# 44con2014.net
KiCad netlist of a schematic drawn in EAGLE
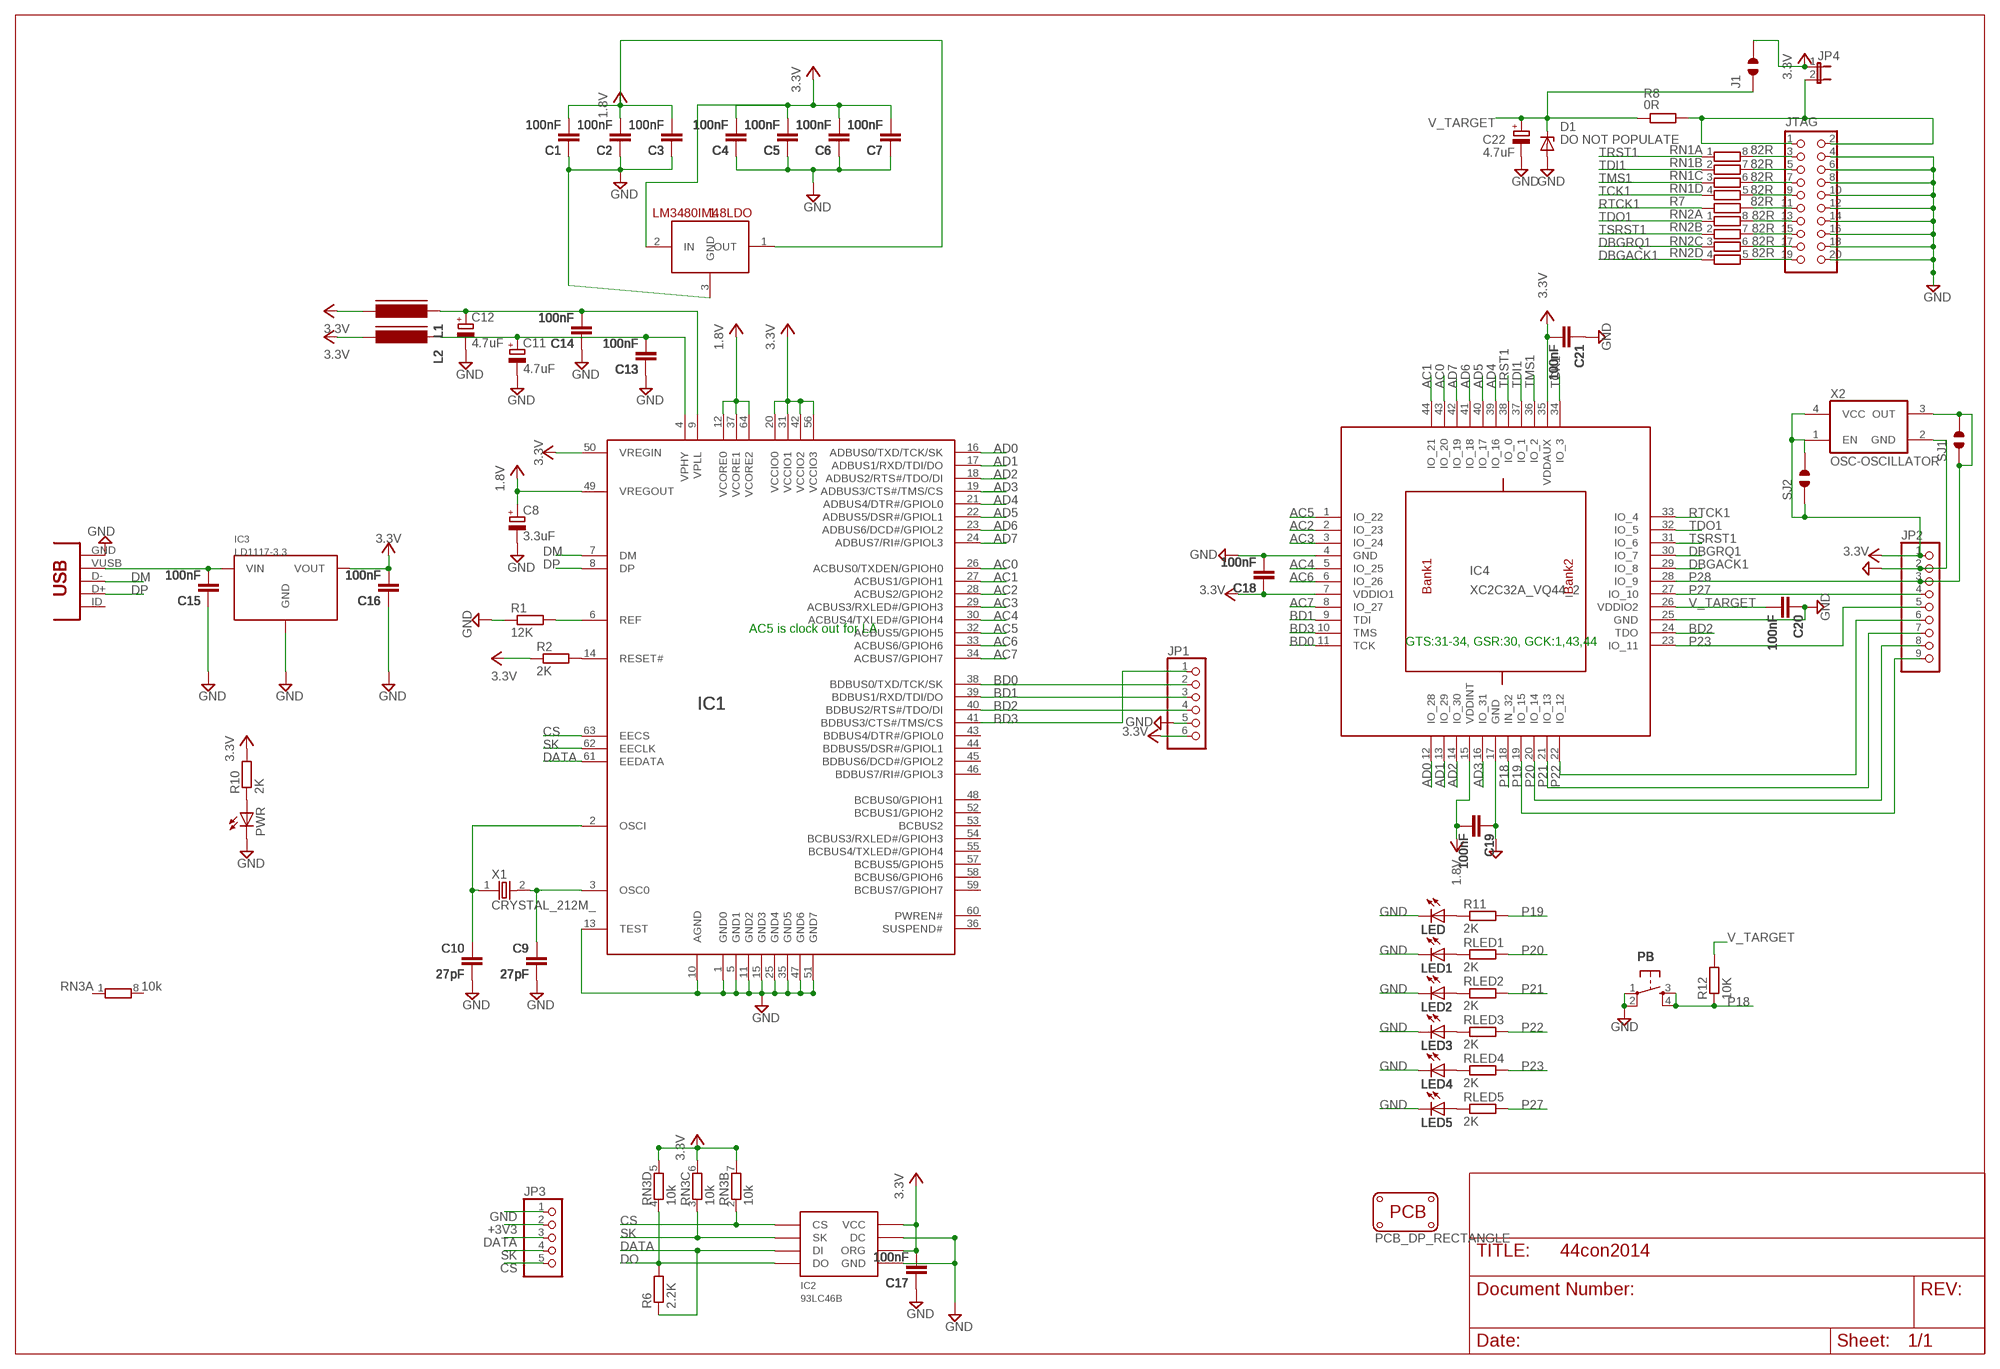
[diagram p0: schematic, sheet 1]

(export (version "E")
  (design (tool "Eeschema 10.0.6"))
  (components
    (comp (ref "1.8LDO")
      (value "LM3480IM4")
      (footprint "eagle-import:SOT23-3")
      (libsource (lib "eagle-import") (part "LM3480IM4"))
    )
    (comp (ref "C1")
      (value "100nF")
      (footprint "eagle-import:C603")
      (libsource (lib "eagle-import") (part "CAPC603"))
    )
    (comp (ref "C2")
      (value "100nF")
      (footprint "eagle-import:C603")
      (libsource (lib "eagle-import") (part "CAPC603"))
    )
    (comp (ref "C3")
      (value "100nF")
      (footprint "eagle-import:C603")
      (libsource (lib "eagle-import") (part "CAPC603"))
    )
    (comp (ref "C4")
      (value "100nF")
      (footprint "eagle-import:C603")
      (libsource (lib "eagle-import") (part "CAPC603"))
    )
    (comp (ref "C5")
      (value "100nF")
      (footprint "eagle-import:C603")
      (libsource (lib "eagle-import") (part "CAPC603"))
    )
    (comp (ref "C6")
      (value "100nF")
      (footprint "eagle-import:C603")
      (libsource (lib "eagle-import") (part "CAPC603"))
    )
    (comp (ref "C7")
      (value "100nF")
      (footprint "eagle-import:C603")
      (libsource (lib "eagle-import") (part "CAPC603"))
    )
    (comp (ref "C8")
      (value "3.3uF")
      (footprint "eagle-import:SMC_A")
      (libsource (lib "eagle-import") (part "CAP_POLSMC_A"))
    )
    (comp (ref "C9")
      (value "27pF")
      (footprint "eagle-import:C603")
      (libsource (lib "eagle-import") (part "CAPC603"))
    )
    (comp (ref "C10")
      (value "27pF")
      (footprint "eagle-import:C603")
      (libsource (lib "eagle-import") (part "CAPC603"))
    )
    (comp (ref "C11")
      (value "4.7uF")
      (footprint "eagle-import:SMC_A")
      (libsource (lib "eagle-import") (part "CAP_POLSMC_A"))
    )
    (comp (ref "C12")
      (value "4.7uF")
      (footprint "eagle-import:SMC_A")
      (libsource (lib "eagle-import") (part "CAP_POLSMC_A"))
    )
    (comp (ref "C13")
      (value "100nF")
      (footprint "eagle-import:C603")
      (libsource (lib "eagle-import") (part "CAPC603"))
    )
    (comp (ref "C14")
      (value "100nF")
      (footprint "eagle-import:C603")
      (libsource (lib "eagle-import") (part "CAPC603"))
    )
    (comp (ref "C15")
      (value "100nF")
      (footprint "eagle-import:C603")
      (libsource (lib "eagle-import") (part "CAPC603"))
    )
    (comp (ref "C16")
      (value "100nF")
      (footprint "eagle-import:C603")
      (libsource (lib "eagle-import") (part "CAPC603"))
    )
    (comp (ref "C17")
      (value "100nF")
      (footprint "eagle-import:C603")
      (libsource (lib "eagle-import") (part "CAPC603"))
    )
    (comp (ref "C18")
      (value "100nF")
      (footprint "eagle-import:C603")
      (libsource (lib "eagle-import") (part "CAPC603"))
    )
    (comp (ref "C19")
      (value "100nF")
      (footprint "eagle-import:C603")
      (libsource (lib "eagle-import") (part "CAPC603"))
    )
    (comp (ref "C20")
      (value "100nF")
      (footprint "eagle-import:C603")
      (libsource (lib "eagle-import") (part "CAPC603"))
    )
    (comp (ref "C21")
      (value "100nF")
      (footprint "eagle-import:C603")
      (libsource (lib "eagle-import") (part "CAPC603"))
    )
    (comp (ref "C22")
      (value "4.7uF")
      (footprint "eagle-import:SMC_A")
      (libsource (lib "eagle-import") (part "CAP_POLSMC_A"))
    )
    (comp (ref "D1")
      (value "DO NOT POPULATE")
      (footprint "eagle-import:SOD-123")
      (libsource (lib "eagle-import") (part "ZENERSOD-123"))
    )
    (comp (ref "IC1")
      (value "FT2232H")
      (footprint "eagle-import:LQFP64")
      (libsource (lib "eagle-import") (part "FT2232H"))
    )
    (comp (ref "IC2")
      (value "93LC46B")
      (footprint "eagle-import:SOIC8")
      (libsource (lib "eagle-import") (part "93C46"))
    )
    (comp (ref "IC3")
      (value "LD1117-3.3")
      (footprint "eagle-import:SOT223")
      (libsource (lib "eagle-import") (part "LD1117-3.3"))
    )
    (comp (ref "IC4")
      (value "XC2C32A_VQ44_2")
      (footprint "eagle-import:VQ44")
      (libsource (lib "eagle-import") (part "XC2C32A_VQ44_2"))
    )
    (comp (ref "J1")
      (value "JUMPER_SOLDER_1X2")
      (footprint "eagle-import:JUMPER_SOLDER_1X2")
      (libsource (lib "eagle-import") (part "JUMPER_SOLDER_1X2"))
    )
    (comp (ref "JP1")
      (value "PINHD-1X6")
      (footprint "eagle-import:1X06")
      (libsource (lib "eagle-import") (part "PINHD-1X6"))
    )
    (comp (ref "JP2")
      (value "PINHD-1X9")
      (footprint "eagle-import:1X09")
      (libsource (lib "eagle-import") (part "PINHD-1X9"))
    )
    (comp (ref "JP3")
      (value "PINHD-1X5")
      (footprint "eagle-import:1X05")
      (libsource (lib "eagle-import") (part "PINHD-1X5"))
    )
    (comp (ref "JP4")
      (value "JP1EJP")
      (footprint "eagle-import:1X02")
      (libsource (lib "eagle-import") (part "JP1EJP"))
    )
    (comp (ref "JTAG")
      (value "CON_HEADER_2X10-SHROUDED")
      (footprint "eagle-import:PINSHRD_PTH_2X10")
      (libsource (lib "eagle-import") (part "CON_HEADER_2X10-SHROUDED"))
    )
    (comp (ref "L1")
      (value "FERRITE_BEAD603")
      (footprint "eagle-import:FB603")
      (libsource (lib "eagle-import") (part "FERRITE_BEAD603"))
    )
    (comp (ref "L2")
      (value "FERRITE_BEAD603")
      (footprint "eagle-import:FB603")
      (libsource (lib "eagle-import") (part "FERRITE_BEAD603"))
    )
    (comp (ref "LED")
      (value "LED805")
      (footprint "eagle-import:LED-805")
      (libsource (lib "eagle-import") (part "LED805"))
    )
    (comp (ref "LED1")
      (value "LED805")
      (footprint "eagle-import:LED-805")
      (libsource (lib "eagle-import") (part "LED805"))
    )
    (comp (ref "LED2")
      (value "LED805")
      (footprint "eagle-import:LED-805")
      (libsource (lib "eagle-import") (part "LED805"))
    )
    (comp (ref "LED3")
      (value "LED805")
      (footprint "eagle-import:LED-805")
      (libsource (lib "eagle-import") (part "LED805"))
    )
    (comp (ref "LED4")
      (value "LED805")
      (footprint "eagle-import:LED-805")
      (libsource (lib "eagle-import") (part "LED805"))
    )
    (comp (ref "LED5")
      (value "LED805")
      (footprint "eagle-import:LED-805")
      (libsource (lib "eagle-import") (part "LED805"))
    )
    (comp (ref "PB")
      (value "SW-SMD-SMALL")
      (footprint "eagle-import:TACT_SWITCH_SMALL")
      (libsource (lib "eagle-import") (part "SW-SMD-SMALL"))
    )
    (comp (ref "PCB3")
      (value "PCB_DP_RECTANGLE")
      (footprint "eagle-import:44CON2014")
      (libsource (lib "eagle-import") (part "PCB_DP_RECTANGLE"))
    )
    (comp (ref "PWR")
      (value "LEDCHIPLED_0805")
      (footprint "eagle-import:CHIPLED_0805")
      (libsource (lib "eagle-import") (part "LEDCHIPLED_0805"))
    )
    (comp (ref "R1")
      (value "12K")
      (footprint "eagle-import:R603")
      (libsource (lib "eagle-import") (part "RESISTORR603"))
    )
    (comp (ref "R2")
      (value "2K")
      (footprint "eagle-import:R603")
      (libsource (lib "eagle-import") (part "RESISTORR603"))
    )
    (comp (ref "R6")
      (value "2.2K")
      (footprint "eagle-import:R603")
      (libsource (lib "eagle-import") (part "RESISTORR603"))
    )
    (comp (ref "R7")
      (value "82R")
      (footprint "eagle-import:R603")
      (libsource (lib "eagle-import") (part "RESISTORR603"))
    )
    (comp (ref "R8")
      (value "0R")
      (footprint "eagle-import:R1206")
      (libsource (lib "eagle-import") (part "RESISTORR1206"))
    )
    (comp (ref "R10")
      (value "2K")
      (footprint "eagle-import:R603")
      (libsource (lib "eagle-import") (part "RESISTORR603"))
    )
    (comp (ref "R11")
      (value "2K")
      (footprint "eagle-import:R603")
      (libsource (lib "eagle-import") (part "RESISTORR603"))
    )
    (comp (ref "R12")
      (value "10K")
      (footprint "eagle-import:R603")
      (libsource (lib "eagle-import") (part "RESISTORR603"))
    )
    (comp (ref "RLED1")
      (value "2K")
      (footprint "eagle-import:R603")
      (libsource (lib "eagle-import") (part "RESISTORR603"))
    )
    (comp (ref "RLED2")
      (value "2K")
      (footprint "eagle-import:R603")
      (libsource (lib "eagle-import") (part "RESISTORR603"))
    )
    (comp (ref "RLED3")
      (value "2K")
      (footprint "eagle-import:R603")
      (libsource (lib "eagle-import") (part "RESISTORR603"))
    )
    (comp (ref "RLED4")
      (value "2K")
      (footprint "eagle-import:R603")
      (libsource (lib "eagle-import") (part "RESISTORR603"))
    )
    (comp (ref "RLED5")
      (value "2K")
      (footprint "eagle-import:R603")
      (libsource (lib "eagle-import") (part "RESISTORR603"))
    )
    (comp (ref "RN1")
      (value "82R")
      (footprint "eagle-import:RN8P-4R-CRA06S")
      (libsource (lib "eagle-import") (part "RNETWORK"))
    )
    (comp (ref "RN2")
      (value "82R")
      (footprint "eagle-import:RN8P-4R-CRA06S")
      (libsource (lib "eagle-import") (part "RNETWORK"))
    )
    (comp (ref "RN3")
      (value "10k")
      (footprint "eagle-import:RN8P-4R-CRA06S")
      (libsource (lib "eagle-import") (part "RNETWORK"))
    )
    (comp (ref "SJ1")
      (value "JUMPER_SOLDER_1X2")
      (footprint "eagle-import:JUMPER_SOLDER_1X2")
      (libsource (lib "eagle-import") (part "JUMPER_SOLDER_1X2"))
    )
    (comp (ref "SJ2")
      (value "JUMPER_SOLDER_1X2")
      (footprint "eagle-import:JUMPER_SOLDER_1X2")
      (libsource (lib "eagle-import") (part "JUMPER_SOLDER_1X2"))
    )
    (comp (ref "USB")
      (value "CON-USB-MINI-BUSB1")
      (footprint "eagle-import:CONN_USB_MINI-B")
      (libsource (lib "eagle-import") (part "CON-USB-MINI-BUSB1"))
    )
    (comp (ref "X1")
      (value "CRYSTAL_212M_")
      (footprint "eagle-import:XTAL_4X6")
      (libsource (lib "eagle-import") (part "OSC-XTAL-12M"))
    )
    (comp (ref "X2")
      (value "OSC-OSCILLATOR")
      (footprint "eagle-import:OSCILLATOR_7X5_SMD")
      (libsource (lib "eagle-import") (part "OSC-OSCILLATOR"))
    )
  )
  (nets
    (net (code "1") (name "/AC0") (class "Default")
      (node (ref "IC1") (pin "26") (pinfunction "ACBUS0/TXDEN/GPIOH0_26") (pintype "bidirectional"))
      (node (ref "IC4") (pin "43") (pinfunction "IO_20_43") (pintype "bidirectional"))
    )
    (net (code "2") (name "/AC1") (class "Default")
      (node (ref "IC1") (pin "27") (pinfunction "ACBUS1/GPIOH1_27") (pintype "bidirectional"))
      (node (ref "IC4") (pin "44") (pinfunction "IO_21_44") (pintype "bidirectional"))
    )
    (net (code "3") (name "/AC2") (class "Default")
      (node (ref "IC1") (pin "28") (pinfunction "ACBUS2/GPIOH2_28") (pintype "bidirectional"))
      (node (ref "IC4") (pin "2") (pinfunction "IO_23_2") (pintype "bidirectional"))
    )
    (net (code "4") (name "/AC3") (class "Default")
      (node (ref "IC1") (pin "29") (pinfunction "ACBUS3/RXLED#/GPIOH3_29") (pintype "bidirectional"))
      (node (ref "IC4") (pin "3") (pinfunction "IO_24_3") (pintype "bidirectional"))
    )
    (net (code "5") (name "/AC4") (class "Default")
      (node (ref "IC1") (pin "30") (pinfunction "ACBUS4/TXLED#/GPIOH4_30") (pintype "bidirectional"))
      (node (ref "IC4") (pin "5") (pinfunction "IO_25_5") (pintype "bidirectional"))
    )
    (net (code "6") (name "/AC5") (class "Default")
      (node (ref "IC1") (pin "32") (pinfunction "ACBUS5/GPIOH5_32") (pintype "bidirectional"))
      (node (ref "IC4") (pin "1") (pinfunction "IO_22_1") (pintype "bidirectional"))
    )
    (net (code "7") (name "/AC6") (class "Default")
      (node (ref "IC1") (pin "33") (pinfunction "ACBUS6/GPIOH6_33") (pintype "bidirectional"))
      (node (ref "IC4") (pin "6") (pinfunction "IO_26_6") (pintype "bidirectional"))
    )
    (net (code "8") (name "/AC7") (class "Default")
      (node (ref "IC1") (pin "34") (pinfunction "ACBUS7/GPIOH7_34") (pintype "bidirectional"))
      (node (ref "IC4") (pin "8") (pinfunction "IO_27_8") (pintype "bidirectional"))
    )
    (net (code "9") (name "/AD0") (class "Default")
      (node (ref "IC1") (pin "16") (pinfunction "ADBUS0/TXD/TCK/SK_16") (pintype "bidirectional"))
      (node (ref "IC4") (pin "12") (pinfunction "IO_28_12") (pintype "bidirectional"))
    )
    (net (code "10") (name "/AD1") (class "Default")
      (node (ref "IC1") (pin "17") (pinfunction "ADBUS1/RXD/TDI/DO_17") (pintype "bidirectional"))
      (node (ref "IC4") (pin "13") (pinfunction "IO_29_13") (pintype "bidirectional"))
    )
    (net (code "11") (name "/AD2") (class "Default")
      (node (ref "IC1") (pin "18") (pinfunction "ADBUS2/RTS#/TDO/DI_18") (pintype "bidirectional"))
      (node (ref "IC4") (pin "14") (pinfunction "IO_30_14") (pintype "bidirectional"))
    )
    (net (code "12") (name "/AD3") (class "Default")
      (node (ref "IC1") (pin "19") (pinfunction "ADBUS3/CTS#/TMS/CS_19") (pintype "bidirectional"))
      (node (ref "IC4") (pin "16") (pinfunction "IO_31_16") (pintype "bidirectional"))
    )
    (net (code "13") (name "/AD4") (class "Default")
      (node (ref "IC1") (pin "21") (pinfunction "ADBUS4/DTR#/GPIOL0_21") (pintype "bidirectional"))
      (node (ref "IC4") (pin "39") (pinfunction "IO_16_39") (pintype "bidirectional"))
    )
    (net (code "14") (name "/AD5") (class "Default")
      (node (ref "IC1") (pin "22") (pinfunction "ADBUS5/DSR#/GPIOL1_22") (pintype "bidirectional"))
      (node (ref "IC4") (pin "40") (pinfunction "IO_17_40") (pintype "bidirectional"))
    )
    (net (code "15") (name "/AD6") (class "Default")
      (node (ref "IC1") (pin "23") (pinfunction "ADBUS6/DCD#/GPIOL2_23") (pintype "bidirectional"))
      (node (ref "IC4") (pin "41") (pinfunction "IO_18_41") (pintype "bidirectional"))
    )
    (net (code "16") (name "/AD7") (class "Default")
      (node (ref "IC1") (pin "24") (pinfunction "ADBUS7/RI#/GPIOL3_24") (pintype "bidirectional"))
      (node (ref "IC4") (pin "42") (pinfunction "IO_19_42") (pintype "bidirectional"))
    )
    (net (code "17") (name "/BD0") (class "Default")
      (node (ref "IC1") (pin "38") (pinfunction "BDBUS0/TXD/TCK/SK_38") (pintype "bidirectional"))
      (node (ref "IC4") (pin "11") (pinfunction "TCK_11") (pintype "input"))
      (node (ref "JP1") (pin "2") (pinfunction "2_2") (pintype "passive"))
    )
    (net (code "18") (name "/BD1") (class "Default")
      (node (ref "IC1") (pin "39") (pinfunction "BDBUS1/RXD/TDI/DO_39") (pintype "bidirectional"))
      (node (ref "IC4") (pin "9") (pinfunction "TDI_9") (pintype "input"))
      (node (ref "JP1") (pin "3") (pinfunction "3_3") (pintype "passive"))
    )
    (net (code "19") (name "/BD2") (class "Default")
      (node (ref "IC1") (pin "40") (pinfunction "BDBUS2/RTS#/TDO/DI_40") (pintype "bidirectional"))
      (node (ref "IC4") (pin "24") (pinfunction "TDO_24") (pintype "output"))
      (node (ref "JP1") (pin "4") (pinfunction "4_4") (pintype "passive"))
    )
    (net (code "20") (name "/BD3") (class "Default")
      (node (ref "IC1") (pin "41") (pinfunction "BDBUS3/CTS#/TMS/CS_41") (pintype "bidirectional"))
      (node (ref "IC4") (pin "10") (pinfunction "TMS_10") (pintype "input"))
      (node (ref "JP1") (pin "1") (pinfunction "1_1") (pintype "passive"))
    )
    (net (code "21") (name "/CS") (class "Default")
      (node (ref "IC1") (pin "63") (pinfunction "EECS_63") (pintype "bidirectional"))
      (node (ref "IC2") (pin "1") (pinfunction "CS_1") (pintype "bidirectional"))
      (node (ref "JP3") (pin "5") (pinfunction "5_5") (pintype "passive"))
      (node (ref "RN3") (pin "2") (pinfunction "1_2") (pintype "passive"))
    )
    (net (code "22") (name "/DATA") (class "Default")
      (node (ref "IC1") (pin "61") (pinfunction "EEDATA_61") (pintype "bidirectional"))
      (node (ref "IC2") (pin "3") (pinfunction "DI_3") (pintype "bidirectional"))
      (node (ref "JP3") (pin "3") (pinfunction "3_3") (pintype "passive"))
      (node (ref "R6") (pin "1") (pinfunction "1_1") (pintype "passive"))
    )
    (net (code "23") (name "/DBGACK1") (class "Default")
      (node (ref "IC4") (pin "29") (pinfunction "IO_8_29") (pintype "bidirectional"))
      (node (ref "RN2") (pin "4") (pinfunction "1_4") (pintype "passive"))
    )
    (net (code "24") (name "/DBGRQ1") (class "Default")
      (node (ref "IC4") (pin "30") (pinfunction "IO_7_30") (pintype "bidirectional"))
      (node (ref "RN2") (pin "3") (pinfunction "1_3") (pintype "passive"))
    )
    (net (code "25") (name "/DM") (class "Default")
      (node (ref "IC1") (pin "7") (pinfunction "DM_7") (pintype "bidirectional"))
      (node (ref "USB") (pin "D-") (pinfunction "D-_D-") (pintype "bidirectional"))
    )
    (net (code "26") (name "/DO") (class "Default")
      (node (ref "IC2") (pin "4") (pinfunction "DO_4") (pintype "bidirectional"))
      (node (ref "R6") (pin "2") (pinfunction "2_2") (pintype "passive"))
      (node (ref "RN3") (pin "4") (pinfunction "1_4") (pintype "passive"))
    )
    (net (code "27") (name "/DP") (class "Default")
      (node (ref "IC1") (pin "8") (pinfunction "DP_8") (pintype "bidirectional"))
      (node (ref "USB") (pin "D+") (pinfunction "D+_D+") (pintype "bidirectional"))
    )
    (net (code "28") (name "/P18") (class "Default")
      (node (ref "IC4") (pin "18") (pinfunction "IN_32_18") (pintype "input"))
      (node (ref "PB") (pin "3") (pinfunction "3_3") (pintype "passive"))
      (node (ref "PB") (pin "4") (pinfunction "4_4") (pintype "passive"))
      (node (ref "R12") (pin "1") (pinfunction "1_1") (pintype "passive"))
    )
    (net (code "29") (name "/P19") (class "Default")
      (node (ref "IC4") (pin "19") (pinfunction "IO_15_19") (pintype "bidirectional"))
      (node (ref "JP2") (pin "9") (pinfunction "9_9") (pintype "passive"))
      (node (ref "R11") (pin "2") (pinfunction "2_2") (pintype "passive"))
    )
    (net (code "30") (name "/P20") (class "Default")
      (node (ref "IC4") (pin "20") (pinfunction "IO_14_20") (pintype "bidirectional"))
      (node (ref "JP2") (pin "8") (pinfunction "8_8") (pintype "passive"))
      (node (ref "RLED1") (pin "2") (pinfunction "2_2") (pintype "passive"))
    )
    (net (code "31") (name "/P21") (class "Default")
      (node (ref "IC4") (pin "21") (pinfunction "IO_13_21") (pintype "bidirectional"))
      (node (ref "JP2") (pin "7") (pinfunction "7_7") (pintype "passive"))
      (node (ref "RLED2") (pin "2") (pinfunction "2_2") (pintype "passive"))
    )
    (net (code "32") (name "/P22") (class "Default")
      (node (ref "IC4") (pin "22") (pinfunction "IO_12_22") (pintype "bidirectional"))
      (node (ref "JP2") (pin "6") (pinfunction "6_6") (pintype "passive"))
      (node (ref "RLED3") (pin "2") (pinfunction "2_2") (pintype "passive"))
    )
    (net (code "33") (name "/P23") (class "Default")
      (node (ref "IC4") (pin "23") (pinfunction "IO_11_23") (pintype "bidirectional"))
      (node (ref "JP2") (pin "5") (pinfunction "5_5") (pintype "passive"))
      (node (ref "RLED4") (pin "2") (pinfunction "2_2") (pintype "passive"))
    )
    (net (code "34") (name "/P27") (class "Default")
      (node (ref "IC4") (pin "27") (pinfunction "IO_10_27") (pintype "bidirectional"))
      (node (ref "JP2") (pin "4") (pinfunction "4_4") (pintype "passive"))
      (node (ref "RLED5") (pin "2") (pinfunction "2_2") (pintype "passive"))
    )
    (net (code "35") (name "/P28") (class "Default")
      (node (ref "IC4") (pin "28") (pinfunction "IO_9_28") (pintype "bidirectional"))
      (node (ref "JP2") (pin "3") (pinfunction "3_3") (pintype "passive"))
      (node (ref "SJ1") (pin "1") (pinfunction "1_1") (pintype "passive"))
      (node (ref "SJ1") (pin "2") (pinfunction "2_2") (pintype "passive"))
      (node (ref "X2") (pin "3") (pinfunction "OUT_3") (pintype "output"))
    )
    (net (code "36") (name "/RTCK1") (class "Default")
      (node (ref "IC4") (pin "33") (pinfunction "IO_4_33") (pintype "bidirectional"))
      (node (ref "R7") (pin "1") (pinfunction "1_1") (pintype "passive"))
    )
    (net (code "37") (name "/SK") (class "Default")
      (node (ref "IC1") (pin "62") (pinfunction "EECLK_62") (pintype "bidirectional"))
      (node (ref "IC2") (pin "2") (pinfunction "SK_2") (pintype "bidirectional"))
      (node (ref "JP3") (pin "4") (pinfunction "4_4") (pintype "passive"))
      (node (ref "RN3") (pin "3") (pinfunction "1_3") (pintype "passive"))
    )
    (net (code "38") (name "/TCK1") (class "Default")
      (node (ref "IC4") (pin "34") (pinfunction "IO_3_34") (pintype "bidirectional"))
      (node (ref "RN1") (pin "4") (pinfunction "1_4") (pintype "passive"))
    )
    (net (code "39") (name "/TDI1") (class "Default")
      (node (ref "IC4") (pin "37") (pinfunction "IO_1_37") (pintype "bidirectional"))
      (node (ref "RN1") (pin "2") (pinfunction "1_2") (pintype "passive"))
    )
    (net (code "40") (name "/TDO1") (class "Default")
      (node (ref "IC4") (pin "32") (pinfunction "IO_5_32") (pintype "bidirectional"))
      (node (ref "RN2") (pin "1") (pinfunction "1_1") (pintype "passive"))
    )
    (net (code "41") (name "/TMS1") (class "Default")
      (node (ref "IC4") (pin "36") (pinfunction "IO_2_36") (pintype "bidirectional"))
      (node (ref "RN1") (pin "3") (pinfunction "1_3") (pintype "passive"))
    )
    (net (code "42") (name "/TRST1") (class "Default")
      (node (ref "IC4") (pin "38") (pinfunction "IO_0_38") (pintype "bidirectional"))
      (node (ref "RN1") (pin "1") (pinfunction "1_1") (pintype "passive"))
    )
    (net (code "43") (name "/TSRST1") (class "Default")
      (node (ref "IC4") (pin "31") (pinfunction "IO_6_31") (pintype "bidirectional"))
      (node (ref "RN2") (pin "2") (pinfunction "1_2") (pintype "passive"))
    )
    (net (code "44") (name "/V_TARGET") (class "Default")
      (node (ref "C20") (pin "2") (pinfunction "2_2") (pintype "passive"))
      (node (ref "C22") (pin "+") (pinfunction "+_+") (pintype "passive"))
      (node (ref "D1") (pin "C") (pinfunction "C_C") (pintype "passive"))
      (node (ref "IC4") (pin "26") (pinfunction "VDDIO2_26") (pintype "power_in"))
      (node (ref "J1") (pin "1") (pinfunction "1_1") (pintype "passive"))
      (node (ref "R12") (pin "2") (pinfunction "2_2") (pintype "passive"))
      (node (ref "R8") (pin "1") (pinfunction "1_1") (pintype "passive"))
    )
    (net (code "45") (name "1.8V") (class "Default")
      (node (ref "1.8LDO") (pin "1") (pinfunction "OUT_1") (pintype "bidirectional"))
      (node (ref "C1") (pin "2") (pinfunction "2_2") (pintype "passive"))
      (node (ref "C19") (pin "2") (pinfunction "2_2") (pintype "passive"))
      (node (ref "C2") (pin "2") (pinfunction "2_2") (pintype "passive"))
      (node (ref "C3") (pin "2") (pinfunction "2_2") (pintype "passive"))
      (node (ref "C8") (pin "+") (pinfunction "+_+") (pintype "passive"))
      (node (ref "IC1") (pin "12") (pinfunction "VCORE0_12") (pintype "bidirectional"))
      (node (ref "IC1") (pin "37") (pinfunction "VCORE1_37") (pintype "bidirectional"))
      (node (ref "IC1") (pin "49") (pinfunction "VREGOUT_49") (pintype "bidirectional"))
      (node (ref "IC1") (pin "64") (pinfunction "VCORE2_64") (pintype "bidirectional"))
      (node (ref "IC4") (pin "15") (pinfunction "VDDINT_15") (pintype "power_in"))
    )
    (net (code "46") (name "3.3V") (class "Default")
      (node (ref "1.8LDO") (pin "2") (pinfunction "IN_2") (pintype "bidirectional"))
      (node (ref "C16") (pin "2") (pinfunction "2_2") (pintype "passive"))
      (node (ref "C17") (pin "2") (pinfunction "2_2") (pintype "passive"))
      (node (ref "C18") (pin "1") (pinfunction "1_1") (pintype "passive"))
      (node (ref "C21") (pin "2") (pinfunction "2_2") (pintype "passive"))
      (node (ref "C4") (pin "2") (pinfunction "2_2") (pintype "passive"))
      (node (ref "C5") (pin "2") (pinfunction "2_2") (pintype "passive"))
      (node (ref "C6") (pin "2") (pinfunction "2_2") (pintype "passive"))
      (node (ref "C7") (pin "2") (pinfunction "2_2") (pintype "passive"))
      (node (ref "IC1") (pin "20") (pinfunction "VCCIO0_20") (pintype "bidirectional"))
      (node (ref "IC1") (pin "31") (pinfunction "VCCIO1_31") (pintype "bidirectional"))
      (node (ref "IC1") (pin "42") (pinfunction "VCCIO2_42") (pintype "bidirectional"))
      (node (ref "IC1") (pin "50") (pinfunction "VREGIN_50") (pintype "bidirectional"))
      (node (ref "IC1") (pin "56") (pinfunction "VCCIO3_56") (pintype "bidirectional"))
      (node (ref "IC2") (pin "6") (pinfunction "ORG_6") (pintype "bidirectional"))
      (node (ref "IC2") (pin "8") (pinfunction "VCC_8") (pintype "bidirectional"))
      (node (ref "IC3") (pin "2") (pinfunction "VOUT_2") (pintype "bidirectional"))
      (node (ref "IC4") (pin "35") (pinfunction "VDDAUX_35") (pintype "power_in"))
      (node (ref "IC4") (pin "7") (pinfunction "VDDIO1_7") (pintype "power_in"))
      (node (ref "J1") (pin "2") (pinfunction "2_2") (pintype "passive"))
      (node (ref "JP1") (pin "6") (pinfunction "6_6") (pintype "passive"))
      (node (ref "JP2") (pin "1") (pinfunction "1_1") (pintype "passive"))
      (node (ref "JP3") (pin "2") (pinfunction "2_2") (pintype "passive"))
      (node (ref "JP4") (pin "1") (pinfunction "1_1") (pintype "passive"))
      (node (ref "L1") (pin "2") (pinfunction "2_2") (pintype "passive"))
      (node (ref "L2") (pin "2") (pinfunction "2_2") (pintype "passive"))
      (node (ref "R10") (pin "2") (pinfunction "2_2") (pintype "passive"))
      (node (ref "R2") (pin "1") (pinfunction "1_1") (pintype "passive"))
      (node (ref "RN3") (pin "5") (pinfunction "2_5") (pintype "passive"))
      (node (ref "RN3") (pin "6") (pinfunction "2_6") (pintype "passive"))
      (node (ref "RN3") (pin "7") (pinfunction "2_7") (pintype "passive"))
      (node (ref "SJ2") (pin "1") (pinfunction "1_1") (pintype "passive"))
      (node (ref "SJ2") (pin "2") (pinfunction "2_2") (pintype "passive"))
      (node (ref "X2") (pin "1") (pinfunction "EN_1") (pintype "input"))
      (node (ref "X2") (pin "4") (pinfunction "VCC_4") (pintype "power_in"))
    )
    (net (code "47") (name "GND") (class "Default")
      (node (ref "1.8LDO") (pin "3") (pinfunction "GND_3") (pintype "bidirectional"))
      (node (ref "C1") (pin "1") (pinfunction "1_1") (pintype "passive"))
      (node (ref "C10") (pin "2") (pinfunction "2_2") (pintype "passive"))
      (node (ref "C11") (pin "-") (pinfunction "-_-") (pintype "passive"))
      (node (ref "C12") (pin "-") (pinfunction "-_-") (pintype "passive"))
      (node (ref "C13") (pin "1") (pinfunction "1_1") (pintype "passive"))
      (node (ref "C14") (pin "1") (pinfunction "1_1") (pintype "passive"))
      (node (ref "C15") (pin "1") (pinfunction "1_1") (pintype "passive"))
      (node (ref "C16") (pin "1") (pinfunction "1_1") (pintype "passive"))
      (node (ref "C17") (pin "1") (pinfunction "1_1") (pintype "passive"))
      (node (ref "C18") (pin "2") (pinfunction "2_2") (pintype "passive"))
      (node (ref "C19") (pin "1") (pinfunction "1_1") (pintype "passive"))
      (node (ref "C2") (pin "1") (pinfunction "1_1") (pintype "passive"))
      (node (ref "C20") (pin "1") (pinfunction "1_1") (pintype "passive"))
      (node (ref "C21") (pin "1") (pinfunction "1_1") (pintype "passive"))
      (node (ref "C22") (pin "-") (pinfunction "-_-") (pintype "passive"))
      (node (ref "C3") (pin "1") (pinfunction "1_1") (pintype "passive"))
      (node (ref "C4") (pin "1") (pinfunction "1_1") (pintype "passive"))
      (node (ref "C5") (pin "1") (pinfunction "1_1") (pintype "passive"))
      (node (ref "C6") (pin "1") (pinfunction "1_1") (pintype "passive"))
      (node (ref "C7") (pin "1") (pinfunction "1_1") (pintype "passive"))
      (node (ref "C8") (pin "-") (pinfunction "-_-") (pintype "passive"))
      (node (ref "C9") (pin "2") (pinfunction "2_2") (pintype "passive"))
      (node (ref "D1") (pin "A") (pinfunction "A_A") (pintype "passive"))
      (node (ref "IC1") (pin "1") (pinfunction "GND0_1") (pintype "bidirectional"))
      (node (ref "IC1") (pin "10") (pinfunction "AGND_10") (pintype "bidirectional"))
      (node (ref "IC1") (pin "11") (pinfunction "GND2_11") (pintype "bidirectional"))
      (node (ref "IC1") (pin "13") (pinfunction "TEST_13") (pintype "bidirectional"))
      (node (ref "IC1") (pin "15") (pinfunction "GND3_15") (pintype "bidirectional"))
      (node (ref "IC1") (pin "25") (pinfunction "GND4_25") (pintype "bidirectional"))
      (node (ref "IC1") (pin "35") (pinfunction "GND5_35") (pintype "bidirectional"))
      (node (ref "IC1") (pin "47") (pinfunction "GND6_47") (pintype "bidirectional"))
      (node (ref "IC1") (pin "5") (pinfunction "GND1_5") (pintype "bidirectional"))
      (node (ref "IC1") (pin "51") (pinfunction "GND7_51") (pintype "bidirectional"))
      (node (ref "IC2") (pin "5") (pinfunction "GND_5") (pintype "bidirectional"))
      (node (ref "IC2") (pin "7") (pinfunction "DC_7") (pintype "bidirectional"))
      (node (ref "IC3") (pin "1") (pinfunction "GND_1") (pintype "bidirectional"))
      (node (ref "IC4") (pin "17") (pinfunction "GND_17") (pintype "power_in"))
      (node (ref "IC4") (pin "25") (pinfunction "GND_25") (pintype "power_in"))
      (node (ref "IC4") (pin "4") (pinfunction "GND_4") (pintype "power_in"))
      (node (ref "JP1") (pin "5") (pinfunction "5_5") (pintype "passive"))
      (node (ref "JP2") (pin "2") (pinfunction "2_2") (pintype "passive"))
      (node (ref "JP3") (pin "1") (pinfunction "1_1") (pintype "passive"))
      (node (ref "JTAG") (pin "10") (pinfunction "10_10") (pintype "passive"))
      (node (ref "JTAG") (pin "12") (pinfunction "12_12") (pintype "passive"))
      (node (ref "JTAG") (pin "14") (pinfunction "14_14") (pintype "passive"))
      (node (ref "JTAG") (pin "16") (pinfunction "16_16") (pintype "passive"))
      (node (ref "JTAG") (pin "18") (pinfunction "18_18") (pintype "passive"))
      (node (ref "JTAG") (pin "20") (pinfunction "20_20") (pintype "passive"))
      (node (ref "JTAG") (pin "4") (pinfunction "4_4") (pintype "passive"))
      (node (ref "JTAG") (pin "6") (pinfunction "6_6") (pintype "passive"))
      (node (ref "JTAG") (pin "8") (pinfunction "8_8") (pintype "passive"))
      (node (ref "LED") (pin "C") (pinfunction "C_C") (pintype "passive"))
      (node (ref "LED1") (pin "C") (pinfunction "C_C") (pintype "passive"))
      (node (ref "LED2") (pin "C") (pinfunction "C_C") (pintype "passive"))
      (node (ref "LED3") (pin "C") (pinfunction "C_C") (pintype "passive"))
      (node (ref "LED4") (pin "C") (pinfunction "C_C") (pintype "passive"))
      (node (ref "LED5") (pin "C") (pinfunction "C_C") (pintype "passive"))
      (node (ref "PB") (pin "1") (pinfunction "1_1") (pintype "passive"))
      (node (ref "PB") (pin "2") (pinfunction "2_2") (pintype "passive"))
      (node (ref "PWR") (pin "C") (pinfunction "C_C") (pintype "passive"))
      (node (ref "R1") (pin "1") (pinfunction "1_1") (pintype "passive"))
      (node (ref "USB") (pin "GND") (pinfunction "GND_GND") (pintype "bidirectional"))
      (node (ref "X2") (pin "2") (pinfunction "GND_2") (pintype "power_in"))
    )
    (net (code "48") (name "Net-(IC1-OSC0)") (class "Default")
      (node (ref "C9") (pin "1") (pinfunction "1_1") (pintype "passive"))
      (node (ref "IC1") (pin "3") (pinfunction "OSC0_3") (pintype "bidirectional"))
      (node (ref "X1") (pin "2") (pinfunction "2_2") (pintype "passive"))
    )
    (net (code "49") (name "Net-(IC1-OSCI)") (class "Default")
      (node (ref "C10") (pin "1") (pinfunction "1_1") (pintype "passive"))
      (node (ref "IC1") (pin "2") (pinfunction "OSCI_2") (pintype "bidirectional"))
      (node (ref "X1") (pin "1") (pinfunction "1_1") (pintype "passive"))
    )
    (net (code "50") (name "Net-(IC1-REF)") (class "Default")
      (node (ref "IC1") (pin "6") (pinfunction "REF_6") (pintype "bidirectional"))
      (node (ref "R1") (pin "2") (pinfunction "2_2") (pintype "passive"))
    )
    (net (code "51") (name "Net-(IC1-RESET#)") (class "Default")
      (node (ref "IC1") (pin "14") (pinfunction "RESET#_14") (pintype "bidirectional"))
      (node (ref "R2") (pin "2") (pinfunction "2_2") (pintype "passive"))
    )
    (net (code "52") (name "Net-(IC1-VPHY)") (class "Default")
      (node (ref "C11") (pin "+") (pinfunction "+_+") (pintype "passive"))
      (node (ref "C13") (pin "2") (pinfunction "2_2") (pintype "passive"))
      (node (ref "IC1") (pin "4") (pinfunction "VPHY_4") (pintype "bidirectional"))
      (node (ref "L2") (pin "1") (pinfunction "1_1") (pintype "passive"))
    )
    (net (code "53") (name "Net-(IC1-VPLL)") (class "Default")
      (node (ref "C12") (pin "+") (pinfunction "+_+") (pintype "passive"))
      (node (ref "C14") (pin "2") (pinfunction "2_2") (pintype "passive"))
      (node (ref "IC1") (pin "9") (pinfunction "VPLL_9") (pintype "bidirectional"))
      (node (ref "L1") (pin "1") (pinfunction "1_1") (pintype "passive"))
    )
    (net (code "54") (name "Net-(IC3-VIN)") (class "Default")
      (node (ref "C15") (pin "2") (pinfunction "2_2") (pintype "passive"))
      (node (ref "IC3") (pin "3") (pinfunction "VIN_3") (pintype "bidirectional"))
      (node (ref "USB") (pin "VUSB") (pinfunction "VUSB_VUSB") (pintype "bidirectional"))
    )
    (net (code "55") (name "Net-(JP4-Pad2)") (class "Default")
      (node (ref "JP4") (pin "2") (pinfunction "2_2") (pintype "passive"))
      (node (ref "JTAG") (pin "1") (pinfunction "1_1") (pintype "passive"))
      (node (ref "JTAG") (pin "2") (pinfunction "2_2") (pintype "passive"))
      (node (ref "R8") (pin "2") (pinfunction "2_2") (pintype "passive"))
    )
    (net (code "56") (name "Net-(JTAG-Pad11)") (class "Default")
      (node (ref "JTAG") (pin "11") (pinfunction "11_11") (pintype "passive"))
      (node (ref "R7") (pin "2") (pinfunction "2_2") (pintype "passive"))
    )
    (net (code "57") (name "Net-(LED-PadA)") (class "Default")
      (node (ref "LED") (pin "A") (pinfunction "A_A") (pintype "passive"))
      (node (ref "R11") (pin "1") (pinfunction "1_1") (pintype "passive"))
    )
    (net (code "58") (name "Net-(LED1-PadA)") (class "Default")
      (node (ref "LED1") (pin "A") (pinfunction "A_A") (pintype "passive"))
      (node (ref "RLED1") (pin "1") (pinfunction "1_1") (pintype "passive"))
    )
    (net (code "59") (name "Net-(LED2-PadA)") (class "Default")
      (node (ref "LED2") (pin "A") (pinfunction "A_A") (pintype "passive"))
      (node (ref "RLED2") (pin "1") (pinfunction "1_1") (pintype "passive"))
    )
    (net (code "60") (name "Net-(LED3-PadA)") (class "Default")
      (node (ref "LED3") (pin "A") (pinfunction "A_A") (pintype "passive"))
      (node (ref "RLED3") (pin "1") (pinfunction "1_1") (pintype "passive"))
    )
    (net (code "61") (name "Net-(LED4-PadA)") (class "Default")
      (node (ref "LED4") (pin "A") (pinfunction "A_A") (pintype "passive"))
      (node (ref "RLED4") (pin "1") (pinfunction "1_1") (pintype "passive"))
    )
    (net (code "62") (name "Net-(LED5-PadA)") (class "Default")
      (node (ref "LED5") (pin "A") (pinfunction "A_A") (pintype "passive"))
      (node (ref "RLED5") (pin "1") (pinfunction "1_1") (pintype "passive"))
    )
    (net (code "63") (name "Net-(PWR-PadA)") (class "Default")
      (node (ref "PWR") (pin "A") (pinfunction "A_A") (pintype "passive"))
      (node (ref "R10") (pin "1") (pinfunction "1_1") (pintype "passive"))
    )
    (net (code "64") (name "Net-(RN1A-2)") (class "Default")
      (node (ref "JTAG") (pin "3") (pinfunction "3_3") (pintype "passive"))
      (node (ref "RN1") (pin "8") (pinfunction "2_8") (pintype "passive"))
    )
    (net (code "65") (name "Net-(RN1B-2)") (class "Default")
      (node (ref "JTAG") (pin "5") (pinfunction "5_5") (pintype "passive"))
      (node (ref "RN1") (pin "7") (pinfunction "2_7") (pintype "passive"))
    )
    (net (code "66") (name "Net-(RN1C-2)") (class "Default")
      (node (ref "JTAG") (pin "7") (pinfunction "7_7") (pintype "passive"))
      (node (ref "RN1") (pin "6") (pinfunction "2_6") (pintype "passive"))
    )
    (net (code "67") (name "Net-(RN1D-2)") (class "Default")
      (node (ref "JTAG") (pin "9") (pinfunction "9_9") (pintype "passive"))
      (node (ref "RN1") (pin "5") (pinfunction "2_5") (pintype "passive"))
    )
    (net (code "68") (name "Net-(RN2A-2)") (class "Default")
      (node (ref "JTAG") (pin "13") (pinfunction "13_13") (pintype "passive"))
      (node (ref "RN2") (pin "8") (pinfunction "2_8") (pintype "passive"))
    )
    (net (code "69") (name "Net-(RN2B-2)") (class "Default")
      (node (ref "JTAG") (pin "15") (pinfunction "15_15") (pintype "passive"))
      (node (ref "RN2") (pin "7") (pinfunction "2_7") (pintype "passive"))
    )
    (net (code "70") (name "Net-(RN2C-2)") (class "Default")
      (node (ref "JTAG") (pin "17") (pinfunction "17_17") (pintype "passive"))
      (node (ref "RN2") (pin "6") (pinfunction "2_6") (pintype "passive"))
    )
    (net (code "71") (name "Net-(RN2D-2)") (class "Default")
      (node (ref "JTAG") (pin "19") (pinfunction "19_19") (pintype "passive"))
      (node (ref "RN2") (pin "5") (pinfunction "2_5") (pintype "passive"))
    )
    (net (code "72") (name "unconnected-(IC1-BCBUS0{slash}GPIOH1-Pad48)") (class "Default")
      (node (ref "IC1") (pin "48") (pinfunction "BCBUS0/GPIOH1_48") (pintype "bidirectional"))
    )
    (net (code "73") (name "unconnected-(IC1-BCBUS1{slash}GPIOH2-Pad52)") (class "Default")
      (node (ref "IC1") (pin "52") (pinfunction "BCBUS1/GPIOH2_52") (pintype "bidirectional"))
    )
    (net (code "74") (name "unconnected-(IC1-BCBUS2-Pad53)") (class "Default")
      (node (ref "IC1") (pin "53") (pinfunction "BCBUS2_53") (pintype "bidirectional"))
    )
    (net (code "75") (name "unconnected-(IC1-BCBUS3{slash}RXLED#{slash}GPIOH3-Pad54)") (class "Default")
      (node (ref "IC1") (pin "54") (pinfunction "BCBUS3/RXLED#/GPIOH3_54") (pintype "bidirectional"))
    )
    (net (code "76") (name "unconnected-(IC1-BCBUS4{slash}TXLED#{slash}GPIOH4-Pad55)") (class "Default")
      (node (ref "IC1") (pin "55") (pinfunction "BCBUS4/TXLED#/GPIOH4_55") (pintype "bidirectional"))
    )
    (net (code "77") (name "unconnected-(IC1-BCBUS5{slash}GPIOH5-Pad57)") (class "Default")
      (node (ref "IC1") (pin "57") (pinfunction "BCBUS5/GPIOH5_57") (pintype "bidirectional"))
    )
    (net (code "78") (name "unconnected-(IC1-BCBUS6{slash}GPIOH6-Pad58)") (class "Default")
      (node (ref "IC1") (pin "58") (pinfunction "BCBUS6/GPIOH6_58") (pintype "bidirectional"))
    )
    (net (code "79") (name "unconnected-(IC1-BCBUS7{slash}GPIOH7-Pad59)") (class "Default")
      (node (ref "IC1") (pin "59") (pinfunction "BCBUS7/GPIOH7_59") (pintype "bidirectional"))
    )
    (net (code "80") (name "unconnected-(IC1-BDBUS4{slash}DTR#{slash}GPIOL0-Pad43)") (class "Default")
      (node (ref "IC1") (pin "43") (pinfunction "BDBUS4/DTR#/GPIOL0_43") (pintype "bidirectional"))
    )
    (net (code "81") (name "unconnected-(IC1-BDBUS5{slash}DSR#{slash}GPIOL1-Pad44)") (class "Default")
      (node (ref "IC1") (pin "44") (pinfunction "BDBUS5/DSR#/GPIOL1_44") (pintype "bidirectional"))
    )
    (net (code "82") (name "unconnected-(IC1-BDBUS6{slash}DCD#{slash}GPIOL2-Pad45)") (class "Default")
      (node (ref "IC1") (pin "45") (pinfunction "BDBUS6/DCD#/GPIOL2_45") (pintype "bidirectional"))
    )
    (net (code "83") (name "unconnected-(IC1-BDBUS7{slash}RI#{slash}GPIOL3-Pad46)") (class "Default")
      (node (ref "IC1") (pin "46") (pinfunction "BDBUS7/RI#/GPIOL3_46") (pintype "bidirectional"))
    )
    (net (code "84") (name "unconnected-(IC1-PWREN#-Pad60)") (class "Default")
      (node (ref "IC1") (pin "60") (pinfunction "PWREN#_60") (pintype "bidirectional"))
    )
    (net (code "85") (name "unconnected-(IC1-SUSPEND#-Pad36)") (class "Default")
      (node (ref "IC1") (pin "36") (pinfunction "SUSPEND#_36") (pintype "bidirectional"))
    )
    (net (code "86") (name "unconnected-(RN3-Pad1)") (class "Default")
      (node (ref "RN3") (pin "1") (pinfunction "1_1") (pintype "passive"))
    )
    (net (code "87") (name "unconnected-(RN3A-2-Pad8)") (class "Default")
      (node (ref "RN3") (pin "8") (pinfunction "2_8") (pintype "passive"))
    )
    (net (code "88") (name "unconnected-(USBB-USBID-PadID)") (class "Default")
      (node (ref "USB") (pin "ID") (pinfunction "USBID_ID") (pintype "bidirectional"))
    )
  )
)
